# Power_System.net
KiCad netlist of a schematic drawn in Altium Designer
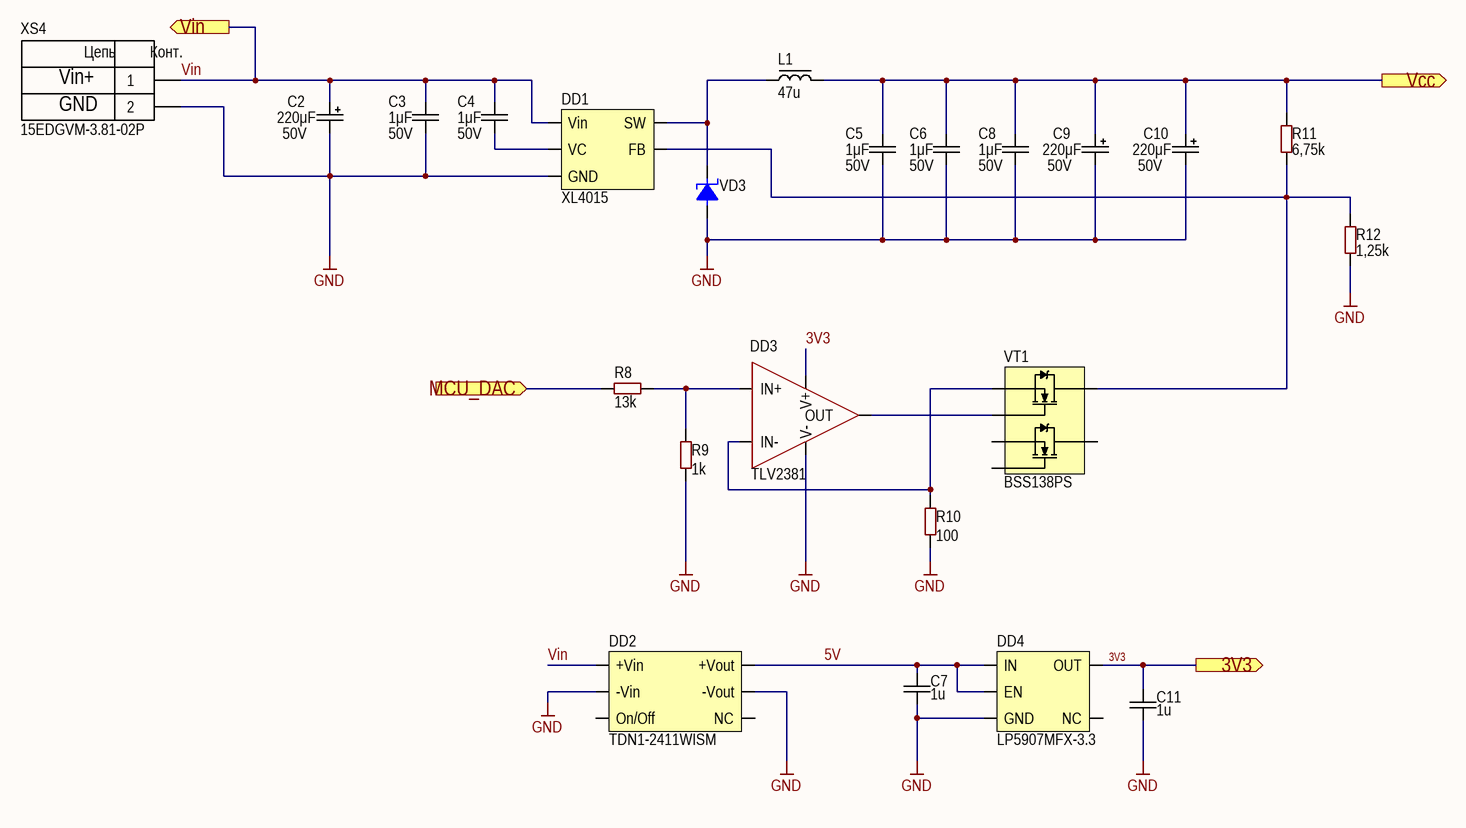
[diagram p0: Power System.SchDoc]

(export (version "E")
  (design (tool "Eeschema 10.0.6"))
  (components
    (comp (ref "C2")
      (value "220μF")
      (footprint "CAP: SMD-G Package(10x10)")
      (fields (field (name "VOLTAGE") "50V"))
      (libsource (lib "capacitor") (part "Aluminium"))
    )
    (comp (ref "C3")
      (value "1μF")
      (footprint "CAP: 0805")
      (fields
        (field (name "MANUFACTURER") "Yageo")
        (field (name "PARTNUMBER") "CC0805KRX7R7BB104")
        (field (name "VALUEMANUFACTURERPARTNUMBER") "Ceramic capacitor, 1μF, X7R, ±10%, 50V, 0805, -55...+125°C")
        (field (name "VOLTAGE") "50V")
      )
      (libsource (lib "capacitor") (part "Ceramic_0805"))
    )
    (comp (ref "C4")
      (value "1μF")
      (footprint "CAP: 0805")
      (fields
        (field (name "MANUFACTURER") "Yageo")
        (field (name "PARTNUMBER") "CC0805KRX7R7BB104")
        (field (name "VALUEMANUFACTURERPARTNUMBER") "Ceramic capacitor, 1μF, X7R, ±10%, 50V, 0805, -55...+125°C")
        (field (name "VOLTAGE") "50V")
      )
      (libsource (lib "capacitor") (part "Ceramic_0805"))
    )
    (comp (ref "C5")
      (value "1μF")
      (footprint "CAP: 0805")
      (fields
        (field (name "MANUFACTURER") "Yageo")
        (field (name "PARTNUMBER") "CC0805KRX7R7BB104")
        (field (name "VALUEMANUFACTURERPARTNUMBER") "Ceramic capacitor, 1μF, X7R, ±10%, 50V, 0805, -55...+125°C")
        (field (name "VOLTAGE") "50V")
      )
      (libsource (lib "capacitor") (part "Ceramic_0805"))
    )
    (comp (ref "C6")
      (value "1μF")
      (footprint "CAP: 0805")
      (fields
        (field (name "MANUFACTURER") "Yageo")
        (field (name "PARTNUMBER") "CC0805KRX7R7BB104")
        (field (name "VALUEMANUFACTURERPARTNUMBER") "Ceramic capacitor, 1μF, X7R, ±10%, 50V, 0805, -55...+125°C")
        (field (name "VOLTAGE") "50V")
      )
      (libsource (lib "capacitor") (part "Ceramic_0805"))
    )
    (comp (ref "C7")
      (value "1u")
      (footprint "CAP: 0603")
      (fields
        (field (name "MANUFACTURER") "Yageo")
        (field (name "PARTNUMBER") "CC0603KRX7R7BB104")
        (field (name "VALUEMANUFACTURERPARTNUMBER") "Ceramic capacitor, 1u, X7R, ±10%, 16V, 0603, -55...+125°C")
      )
      (libsource (lib "capacitor") (part "Ceramic_0603"))
    )
    (comp (ref "C8")
      (value "1μF")
      (footprint "CAP: 0805")
      (fields
        (field (name "MANUFACTURER") "Yageo")
        (field (name "PARTNUMBER") "CC0805KRX7R7BB104")
        (field (name "VALUEMANUFACTURERPARTNUMBER") "Ceramic capacitor, 1μF, X7R, ±10%, 50V, 0805, -55...+125°C")
        (field (name "VOLTAGE") "50V")
      )
      (libsource (lib "capacitor") (part "Ceramic_0805"))
    )
    (comp (ref "C9")
      (value "220μF")
      (footprint "CAP: SMD-G Package(10x10)")
      (fields (field (name "VOLTAGE") "50V"))
      (libsource (lib "capacitor") (part "Aluminium"))
    )
    (comp (ref "C10")
      (value "220μF")
      (footprint "CAP: SMD-G Package(10x10)")
      (fields (field (name "VOLTAGE") "50V"))
      (libsource (lib "capacitor") (part "Aluminium"))
    )
    (comp (ref "C11")
      (value "1u")
      (footprint "CAP: 0603")
      (fields
        (field (name "MANUFACTURER") "Yageo")
        (field (name "PARTNUMBER") "CC0603KRX7R7BB104")
        (field (name "VALUEMANUFACTURERPARTNUMBER") "Ceramic capacitor, 1u, X7R, ±10%, 16V, 0603, -55...+125°C")
      )
      (libsource (lib "capacitor") (part "Ceramic_0603"))
    )
    (comp (ref "DD1")
      (value "XL4015")
      (footprint "TO263-5L")
      (description "Buck DC-DC")
      (libsource (lib "ic-power-supply") (part "XL4015"))
    )
    (comp (ref "DD2")
      (value "TDN1-2411WISM")
      (footprint "TDN1-2411WISM")
      (description "DC-DC converter")
      (libsource (lib "ic-power-supply") (part "TDN1-2411WISM"))
    )
    (comp (ref "DD3")
      (value "TLV2381")
      (footprint "SOT23-5")
      (description "OPAmp")
      (libsource (lib "ic-amplifier") (part "TLV2381"))
    )
    (comp (ref "DD4")
      (value "LP5907MFX-3.3")
      (footprint "SOT23-5")
      (description "LDO 250 mA")
      (libsource (lib "ic-power-supply") (part "LP5907MFX-3.3"))
    )
    (comp (ref "L1") (value "47u") (footprint "IND: HM") (libsource (lib "inductor") (part "Inductor(HM)")))
    (comp (ref "R8")
      (value "13k")
      (footprint "RES: 0603")
      (fields
        (field (name "MANUFACTURER") "Yageo")
        (field (name "PARTNUMBER") "RC0603JR-07100RL")
        (field (name "VALUEMANUFACTURERPARTNUMBER") "Resistor film, 13k, ±5%, 0603, 0.1W, -55...+125°C")
      )
      (libsource (lib "") (part "Resistor_0603_2"))
    )
    (comp (ref "R9")
      (value "1k")
      (footprint "RES: 0603")
      (fields
        (field (name "MANUFACTURER") "Yageo")
        (field (name "PARTNUMBER") "RC0603JR-07100RL")
        (field (name "VALUEMANUFACTURERPARTNUMBER") "Resistor film, 1k, ±5%, 0603, 0.1W, -55...+125°C")
      )
      (libsource (lib "resistor") (part "Resistor_0603"))
    )
    (comp (ref "R10")
      (value "100")
      (footprint "RES: 0603")
      (fields
        (field (name "MANUFACTURER") "Yageo")
        (field (name "PARTNUMBER") "RC0603JR-07100RL")
        (field (name "VALUEMANUFACTURERPARTNUMBER") "Resistor film, 100, ±5%, 0603, 0.1W, -55...+125°C")
      )
      (libsource (lib "resistor") (part "Resistor_0603"))
    )
    (comp (ref "R11")
      (value "6,75k")
      (footprint "RES: 0603")
      (fields
        (field (name "MANUFACTURER") "Yageo")
        (field (name "PARTNUMBER") "RC0603JR-07100RL")
        (field (name "VALUEMANUFACTURERPARTNUMBER") "Resistor film, 6,75k, ±5%, 0603, 0.1W, -55...+125°C")
      )
      (libsource (lib "") (part "Resistor_0603_1"))
    )
    (comp (ref "R12")
      (value "1,25k")
      (footprint "RES: 0603")
      (fields
        (field (name "MANUFACTURER") "Yageo")
        (field (name "PARTNUMBER") "RC0603JR-07100RL")
        (field (name "VALUEMANUFACTURERPARTNUMBER") "Resistor film, 1,25k, ±5%, 0603, 0.1W, -55...+125°C")
      )
      (libsource (lib "") (part "Resistor_0603_1"))
    )
    (comp (ref "VD3")
      (value "STPS1045DEE")
      (footprint "PowerFLAT(3.3x3.3)")
      (description "45V,10A Schottky")
      (libsource (lib "diode") (part "STPS1045DEE"))
    )
    (comp (ref "VT1")
      (value "BSS138PS")
      (footprint "SOT363")
      (libsource (lib "transistor") (part "BSS138PS"))
    )
    (comp (ref "XS4")
      (value "15EDGVM-3.81-02P")
      (footprint "CON: 15EDGVM-3.81-02P")
      (libsource (lib "connector") (part "15EDGVM-3.81-02P"))
    )
  )
  (nets
    (net (code "1") (name "/3V3") (class "Default")
      (node (ref "C11") (pin "2") (pinfunction "2_2") (pintype "passive"))
      (node (ref "DD3") (pin "5") (pinfunction "V+_5") (pintype "passive"))
      (node (ref "DD4") (pin "5") (pinfunction "OUT_5") (pintype "passive"))
    )
    (net (code "2") (name "/5V") (class "Default")
      (node (ref "C7") (pin "2") (pinfunction "2_2") (pintype "passive"))
      (node (ref "DD2") (pin "7") (pinfunction "+Vout_7") (pintype "passive"))
      (node (ref "DD4") (pin "1") (pinfunction "IN_1") (pintype "passive"))
      (node (ref "DD4") (pin "3") (pinfunction "EN_3") (pintype "passive"))
    )
    (net (code "3") (name "/MCU_DAC") (class "Default")
      (node (ref "R8") (pin "2") (pinfunction "2_2") (pintype "passive"))
    )
    (net (code "4") (name "/Vcc") (class "Default")
      (node (ref "C10") (pin "1") (pinfunction "1_1") (pintype "passive"))
      (node (ref "C5") (pin "2") (pinfunction "2_2") (pintype "passive"))
      (node (ref "C6") (pin "2") (pinfunction "2_2") (pintype "passive"))
      (node (ref "C8") (pin "2") (pinfunction "2_2") (pintype "passive"))
      (node (ref "C9") (pin "1") (pinfunction "1_1") (pintype "passive"))
      (node (ref "L1") (pin "2") (pinfunction "2_2") (pintype "passive"))
      (node (ref "R11") (pin "2") (pinfunction "2_2") (pintype "passive"))
    )
    (net (code "5") (name "/Vin") (class "Default")
      (node (ref "C2") (pin "1") (pinfunction "1_1") (pintype "passive"))
      (node (ref "C3") (pin "2") (pinfunction "2_2") (pintype "passive"))
      (node (ref "C4") (pin "2") (pinfunction "2_2") (pintype "passive"))
      (node (ref "DD1") (pin "5") (pinfunction "Vin_5") (pintype "passive"))
      (node (ref "DD2") (pin "1") (pinfunction "+Vin_1") (pintype "passive"))
      (node (ref "XS4") (pin "1") (pinfunction "1_1") (pintype "passive"))
    )
    (net (code "6") (name "GND") (class "Default")
      (node (ref "C10") (pin "2") (pinfunction "2_2") (pintype "passive"))
      (node (ref "C11") (pin "1") (pinfunction "1_1") (pintype "passive"))
      (node (ref "C2") (pin "2") (pinfunction "2_2") (pintype "passive"))
      (node (ref "C3") (pin "1") (pinfunction "1_1") (pintype "passive"))
      (node (ref "C5") (pin "1") (pinfunction "1_1") (pintype "passive"))
      (node (ref "C6") (pin "1") (pinfunction "1_1") (pintype "passive"))
      (node (ref "C7") (pin "1") (pinfunction "1_1") (pintype "passive"))
      (node (ref "C8") (pin "1") (pinfunction "1_1") (pintype "passive"))
      (node (ref "C9") (pin "2") (pinfunction "2_2") (pintype "passive"))
      (node (ref "DD1") (pin "1") (pinfunction "GND_1") (pintype "passive"))
      (node (ref "DD2") (pin "2") (pinfunction "-Vin_2") (pintype "passive"))
      (node (ref "DD2") (pin "6") (pinfunction "-Vout_6") (pintype "passive"))
      (node (ref "DD3") (pin "2") (pinfunction "V-_2") (pintype "passive"))
      (node (ref "DD4") (pin "2") (pinfunction "GND_2") (pintype "passive"))
      (node (ref "R10") (pin "2") (pinfunction "2_2") (pintype "passive"))
      (node (ref "R12") (pin "1") (pinfunction "1_1") (pintype "passive"))
      (node (ref "R9") (pin "2") (pinfunction "2_2") (pintype "passive"))
      (node (ref "VD3") (pin "1") (pinfunction "1_1") (pintype "passive"))
      (node (ref "XS4") (pin "2") (pinfunction "2_2") (pintype "passive"))
    )
    (net (code "7") (name "Net-(DD1-FB)") (class "Default")
      (node (ref "DD1") (pin "2") (pinfunction "FB_2") (pintype "passive"))
      (node (ref "R11") (pin "1") (pinfunction "1_1") (pintype "passive"))
      (node (ref "R12") (pin "2") (pinfunction "2_2") (pintype "passive"))
      (node (ref "VT1") (pin "6") (pinfunction "D1_6") (pintype "passive"))
    )
    (net (code "8") (name "Net-(DD1-SW)") (class "Default")
      (node (ref "DD1") (pin "3") (pinfunction "SW_3") (pintype "passive"))
      (node (ref "L1") (pin "1") (pinfunction "1_1") (pintype "passive"))
      (node (ref "VD3") (pin "2") (pinfunction "2_2") (pintype "passive"))
    )
    (net (code "9") (name "Net-(DD1-VC)") (class "Default")
      (node (ref "C4") (pin "1") (pinfunction "1_1") (pintype "passive"))
      (node (ref "DD1") (pin "4") (pinfunction "VC_4") (pintype "passive"))
    )
    (net (code "10") (name "Net-(DD3-IN+)") (class "Default")
      (node (ref "DD3") (pin "3") (pinfunction "IN+_3") (pintype "passive"))
      (node (ref "R8") (pin "1") (pinfunction "1_1") (pintype "passive"))
      (node (ref "R9") (pin "1") (pinfunction "1_1") (pintype "passive"))
    )
    (net (code "11") (name "Net-(DD3-IN-)") (class "Default")
      (node (ref "DD3") (pin "4") (pinfunction "IN-_4") (pintype "passive"))
      (node (ref "R10") (pin "1") (pinfunction "1_1") (pintype "passive"))
      (node (ref "VT1") (pin "1") (pinfunction "S1_1") (pintype "passive"))
    )
    (net (code "12") (name "Net-(DD3-OUT)") (class "Default")
      (node (ref "DD3") (pin "1") (pinfunction "OUT_1") (pintype "passive"))
      (node (ref "VT1") (pin "2") (pinfunction "G1_2") (pintype "passive"))
    )
    (net (code "13") (name "unconnected-(DD2-NC-Pad5)") (class "Default")
      (node (ref "DD2") (pin "5") (pinfunction "NC_5") (pintype "passive"))
    )
    (net (code "14") (name "unconnected-(DD2-On{slash}Off-Pad4)") (class "Default")
      (node (ref "DD2") (pin "4") (pinfunction "On/Off_4") (pintype "passive"))
    )
    (net (code "15") (name "unconnected-(DD4-NC-Pad4)") (class "Default")
      (node (ref "DD4") (pin "4") (pinfunction "NC_4") (pintype "passive"))
    )
    (net (code "16") (name "unconnected-(VT1-D2-Pad3)") (class "Default")
      (node (ref "VT1") (pin "3") (pinfunction "D2_3") (pintype "passive"))
    )
    (net (code "17") (name "unconnected-(VT1-G2-Pad5)") (class "Default")
      (node (ref "VT1") (pin "5") (pinfunction "G2_5") (pintype "passive"))
    )
    (net (code "18") (name "unconnected-(VT1-S2-Pad4)") (class "Default")
      (node (ref "VT1") (pin "4") (pinfunction "S2_4") (pintype "passive"))
    )
  )
)
